# coil.net
KiCad netlist of a schematic drawn in Altium Designer
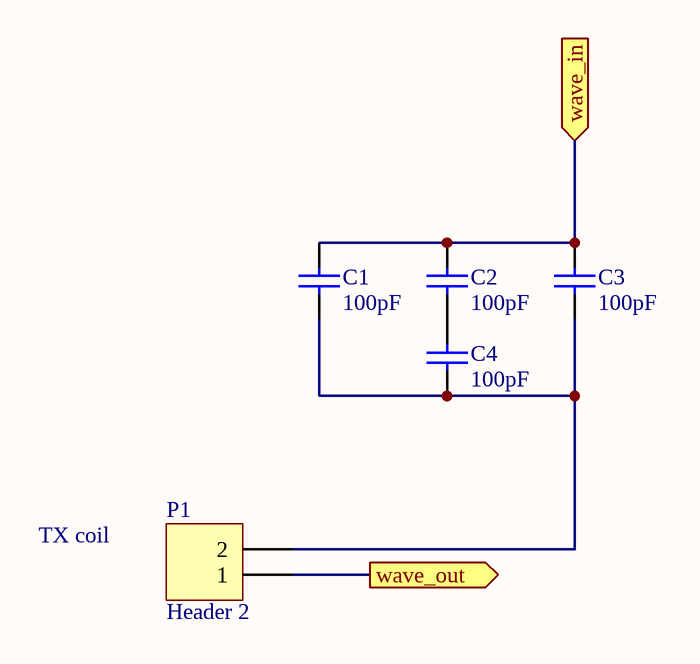
[diagram p0: coil.SchDoc]

(export (version "E")
  (design (tool "Eeschema 10.0.6"))
  (components
    (comp (ref "C1")
      (value "100pF")
      (footprint "0603")
      (description "Ceramic Capacitor (Surface Mount)")
      (fields (field (name "MANUFACTURER") "Generic Ceramic Chip Cap (TBD)") (field (name "Comment") "Cap"))
      (libsource (lib "maglib") (part "Cap"))
    )
    (comp (ref "C2")
      (value "100pF")
      (footprint "0603")
      (description "Ceramic Capacitor (Surface Mount)")
      (fields (field (name "MANUFACTURER") "Generic Ceramic Chip Cap (TBD)") (field (name "Comment") "Cap"))
      (libsource (lib "maglib") (part "Cap"))
    )
    (comp (ref "C3")
      (value "100pF")
      (footprint "0603")
      (description "Ceramic Capacitor (Surface Mount)")
      (fields (field (name "MANUFACTURER") "Generic Ceramic Chip Cap (TBD)") (field (name "Comment") "Cap"))
      (libsource (lib "maglib") (part "Cap"))
    )
    (comp (ref "C4")
      (value "100pF")
      (footprint "0603")
      (description "Ceramic Capacitor (Surface Mount)")
      (fields (field (name "MANUFACTURER") "Generic Ceramic Chip Cap (TBD)") (field (name "Comment") "Cap"))
      (libsource (lib "maglib") (part "Cap"))
    )
    (comp (ref "P1")
      (value "Header 2")
      (footprint "HDR1X2")
      (description "Header, 2-Pin")
      (fields (field (name "PUBLISHER") "Altium Limited"))
      (libsource (lib "Miscellaneous Connectors") (part "Header 2"))
    )
  )
  (nets
    (net (code "1") (name "/wave_in") (class "Default")
      (node (ref "C1") (pin "2") (pinfunction "2_2") (pintype "passive"))
      (node (ref "C2") (pin "2") (pinfunction "2_2") (pintype "passive"))
      (node (ref "C3") (pin "2") (pinfunction "2_2") (pintype "passive"))
    )
    (net (code "2") (name "/wave_out") (class "Default")
      (node (ref "P1") (pin "1") (pinfunction "1_1") (pintype "passive"))
    )
    (net (code "3") (name "Net-(C1-Pad1)") (class "Default")
      (node (ref "C1") (pin "1") (pinfunction "1_1") (pintype "passive"))
      (node (ref "C3") (pin "1") (pinfunction "1_1") (pintype "passive"))
      (node (ref "C4") (pin "1") (pinfunction "1_1") (pintype "passive"))
      (node (ref "P1") (pin "2") (pinfunction "2_2") (pintype "passive"))
    )
    (net (code "4") (name "Net-(C2-Pad1)") (class "Default")
      (node (ref "C2") (pin "1") (pinfunction "1_1") (pintype "passive"))
      (node (ref "C4") (pin "2") (pinfunction "2_2") (pintype "passive"))
    )
  )
)
